# cmoy.net
KiCad netlist of a schematic drawn in EAGLE
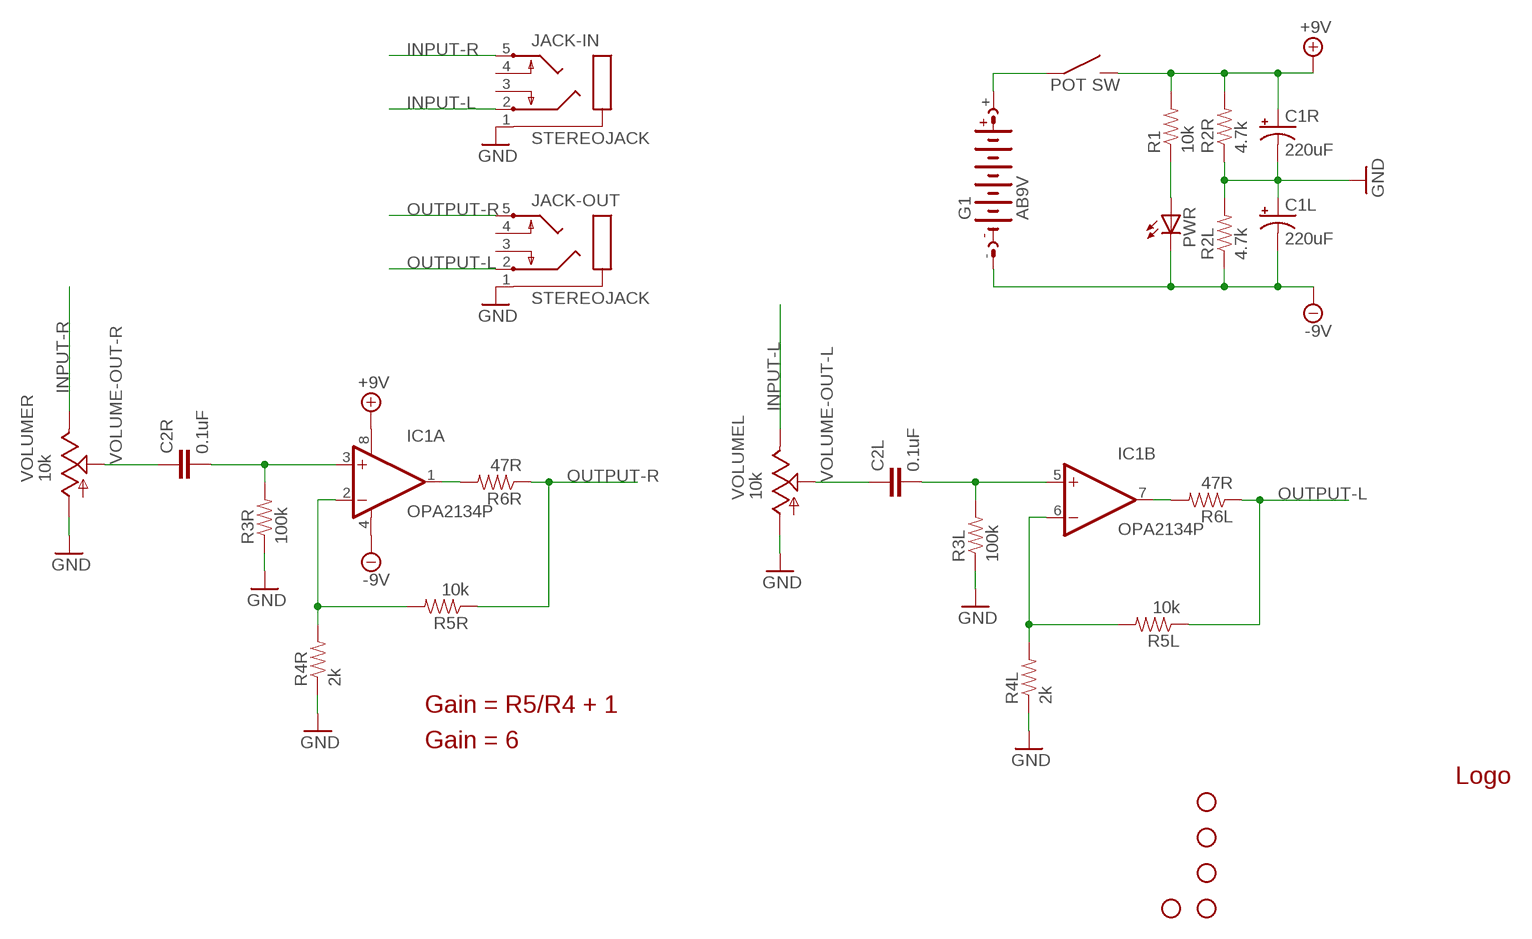
[diagram p0: schematic, sheet 1]

(export (version "E")
  (design (tool "Eeschema 10.0.6"))
  (components
    (comp (ref "C1L")
      (value "220uF")
      (footprint "eagle-import:CPOL-RADIAL-6.3MM")
      (libsource (lib "eagle-import") (part "CAP_POL-RADIAL-6.3MM"))
    )
    (comp (ref "C1R")
      (value "220uF")
      (footprint "eagle-import:CPOL-RADIAL-6.3MM")
      (libsource (lib "eagle-import") (part "CAP_POL-RADIAL-6.3MM"))
    )
    (comp (ref "C2L")
      (value "0.1uF")
      (footprint "eagle-import:CAP-PTH-VIMA-MKS2C031001A00KSSD")
      (libsource (lib "eagle-import") (part "CAP-VIMA-MKS2D031001"))
    )
    (comp (ref "C2R")
      (value "0.1uF")
      (footprint "eagle-import:CAP-PTH-VIMA-MKS2C031001A00KSSD")
      (libsource (lib "eagle-import") (part "CAP-VIMA-MKS2D031001"))
    )
    (comp (ref "G1")
      (value "AB9V")
      (footprint "eagle-import:AB9V")
      (libsource (lib "eagle-import") (part "AB9V"))
    )
    (comp (ref "IC1")
      (value "OPA2134P")
      (footprint "eagle-import:DIL-8")
      (libsource (lib "eagle-import") (part "OPA2134P"))
    )
    (comp (ref "JACK-IN")
      (value "STEREOJACK")
      (footprint "eagle-import:STX3100")
      (libsource (lib "eagle-import") (part "STEREOJACK"))
    )
    (comp (ref "JACK-OUT")
      (value "STEREOJACK")
      (footprint "eagle-import:STX3100")
      (libsource (lib "eagle-import") (part "STEREOJACK"))
    )
    (comp (ref "JP1")
      (value "STAND-OFF")
      (footprint "eagle-import:STAND-OFF")
      (libsource (lib "eagle-import") (part "STAND-OFF"))
    )
    (comp (ref "JP2")
      (value "STAND-OFF")
      (footprint "eagle-import:STAND-OFF")
      (libsource (lib "eagle-import") (part "STAND-OFF"))
    )
    (comp (ref "JP3")
      (value "STAND-OFF")
      (footprint "eagle-import:STAND-OFF")
      (libsource (lib "eagle-import") (part "STAND-OFF"))
    )
    (comp (ref "JP4")
      (value "STAND-OFF")
      (footprint "eagle-import:STAND-OFF")
      (libsource (lib "eagle-import") (part "STAND-OFF"))
    )
    (comp (ref "JP5")
      (value "STAND-OFF")
      (footprint "eagle-import:STAND-OFF")
      (libsource (lib "eagle-import") (part "STAND-OFF"))
    )
    (comp (ref "PWR")
      (value "LED-3MM-MINUS")
      (footprint "eagle-import:LED3MM-MINUS")
      (libsource (lib "eagle-import") (part "LED-3MM-MINUS"))
    )
    (comp (ref "R1")
      (value "10k")
      (footprint "eagle-import:1_6W-RES-OUTLINE")
      (libsource (lib "eagle-import") (part "RESISTOR-PTH-1/6W-OUTLINE"))
    )
    (comp (ref "R2L")
      (value "4.7k")
      (footprint "eagle-import:1_6W-RES-OUTLINE")
      (libsource (lib "eagle-import") (part "RESISTOR-PTH-1/6W-OUTLINE"))
    )
    (comp (ref "R2R")
      (value "4.7k")
      (footprint "eagle-import:1_6W-RES-OUTLINE")
      (libsource (lib "eagle-import") (part "RESISTOR-PTH-1/6W-OUTLINE"))
    )
    (comp (ref "R3L")
      (value "100k")
      (footprint "eagle-import:1_4W-RES-OUTLINE")
      (libsource (lib "eagle-import") (part "RESISTOR-PTH-1/4W-OUTLINE"))
    )
    (comp (ref "R3R")
      (value "100k")
      (footprint "eagle-import:1_4W-RES-OUTLINE")
      (libsource (lib "eagle-import") (part "RESISTOR-PTH-1/4W-OUTLINE"))
    )
    (comp (ref "R4L")
      (value "2k")
      (footprint "eagle-import:1_4W-RES-OUTLINE")
      (libsource (lib "eagle-import") (part "RESISTOR-PTH-1/4W-OUTLINE"))
    )
    (comp (ref "R4R")
      (value "2k")
      (footprint "eagle-import:1_4W-RES-OUTLINE")
      (libsource (lib "eagle-import") (part "RESISTOR-PTH-1/4W-OUTLINE"))
    )
    (comp (ref "R5L")
      (value "10k")
      (footprint "eagle-import:1_4W-RES-OUTLINE")
      (libsource (lib "eagle-import") (part "RESISTOR-PTH-1/4W-OUTLINE"))
    )
    (comp (ref "R5R")
      (value "10k")
      (footprint "eagle-import:1_4W-RES-OUTLINE")
      (libsource (lib "eagle-import") (part "RESISTOR-PTH-1/4W-OUTLINE"))
    )
    (comp (ref "R6L")
      (value "47R")
      (footprint "eagle-import:1_4W-RES-OUTLINE")
      (libsource (lib "eagle-import") (part "RESISTOR-PTH-1/4W-OUTLINE"))
    )
    (comp (ref "R6R")
      (value "47R")
      (footprint "eagle-import:1_4W-RES-OUTLINE")
      (libsource (lib "eagle-import") (part "RESISTOR-PTH-1/4W-OUTLINE"))
    )
    (comp (ref "U$1")
      (value "OSHW-LOGO-OUTLINE")
      (footprint "eagle-import:OSHW-LOGO-OUTLINE")
      (libsource (lib "eagle-import") (part "OSHW-LOGO-OUTLINE"))
    )
    (comp (ref "VOLUME")
      (value "10k")
      (footprint "eagle-import:ALPS_RK0971221Z0X")
      (libsource (lib "eagle-import") (part "ALPS_RK0971221Z0N"))
    )
  )
  (nets
    (net (code "1") (name "+9V") (class "Default")
      (node (ref "C1R") (pin "1") (pinfunction "+_1") (pintype "passive"))
      (node (ref "IC1") (pin "8") (pinfunction "V+_8") (pintype "power_in"))
      (node (ref "R1") (pin "2") (pinfunction "2_2") (pintype "passive"))
      (node (ref "R2R") (pin "2") (pinfunction "2_2") (pintype "passive"))
      (node (ref "VOLUME") (pin "S2") (pinfunction "S2_S2") (pintype "power_in"))
    )
    (net (code "2") (name "-9V") (class "Default")
      (node (ref "C1L") (pin "2") (pinfunction "-_2") (pintype "passive"))
      (node (ref "G1") (pin "-") (pinfunction "-_-") (pintype "passive"))
      (node (ref "IC1") (pin "4") (pinfunction "V-_4") (pintype "power_in"))
      (node (ref "PWR") (pin "K") (pinfunction "C_K") (pintype "passive"))
      (node (ref "R2L") (pin "1") (pinfunction "1_1") (pintype "passive"))
    )
    (net (code "3") (name "/INPUT-L") (class "Default")
      (node (ref "JACK-IN") (pin "2") (pinfunction "2_2") (pintype "passive"))
      (node (ref "VOLUME") (pin "I1") (pinfunction "3_I1") (pintype "passive"))
    )
    (net (code "4") (name "/INPUT-R") (class "Default")
      (node (ref "JACK-IN") (pin "5") (pinfunction "5_5") (pintype "passive"))
      (node (ref "VOLUME") (pin "I2") (pinfunction "3_I2") (pintype "passive"))
    )
    (net (code "5") (name "/OUTPUT-L") (class "Default")
      (node (ref "JACK-OUT") (pin "2") (pinfunction "2_2") (pintype "passive"))
      (node (ref "R5L") (pin "P$1") (pinfunction "1_P$1") (pintype "passive"))
      (node (ref "R6L") (pin "P$1") (pinfunction "1_P$1") (pintype "passive"))
    )
    (net (code "6") (name "/OUTPUT-R") (class "Default")
      (node (ref "JACK-OUT") (pin "5") (pinfunction "5_5") (pintype "passive"))
      (node (ref "R5R") (pin "P$1") (pinfunction "1_P$1") (pintype "passive"))
      (node (ref "R6R") (pin "P$1") (pinfunction "1_P$1") (pintype "passive"))
    )
    (net (code "7") (name "/VOLUME-OUT-L") (class "Default")
      (node (ref "C2L") (pin "1") (pinfunction "1_1") (pintype "passive"))
      (node (ref "VOLUME") (pin "O1") (pinfunction "2_O1") (pintype "passive"))
    )
    (net (code "8") (name "/VOLUME-OUT-R") (class "Default")
      (node (ref "C2R") (pin "1") (pinfunction "1_1") (pintype "passive"))
      (node (ref "VOLUME") (pin "O2") (pinfunction "2_O2") (pintype "passive"))
    )
    (net (code "9") (name "GND") (class "Default")
      (node (ref "C1L") (pin "1") (pinfunction "+_1") (pintype "passive"))
      (node (ref "C1R") (pin "2") (pinfunction "-_2") (pintype "passive"))
      (node (ref "JACK-IN") (pin "1") (pinfunction "1_1") (pintype "passive"))
      (node (ref "JACK-OUT") (pin "1") (pinfunction "1_1") (pintype "passive"))
      (node (ref "R2L") (pin "2") (pinfunction "2_2") (pintype "passive"))
      (node (ref "R2R") (pin "1") (pinfunction "1_1") (pintype "passive"))
      (node (ref "R3L") (pin "P$1") (pinfunction "1_P$1") (pintype "passive"))
      (node (ref "R3R") (pin "P$1") (pinfunction "1_P$1") (pintype "passive"))
      (node (ref "R4L") (pin "P$1") (pinfunction "1_P$1") (pintype "passive"))
      (node (ref "R4R") (pin "P$1") (pinfunction "1_P$1") (pintype "passive"))
      (node (ref "VOLUME") (pin "G1") (pinfunction "1_G1") (pintype "passive"))
      (node (ref "VOLUME") (pin "G2") (pinfunction "1_G2") (pintype "passive"))
    )
    (net (code "10") (name "Net-(G1-Pad+)") (class "Default")
      (node (ref "G1") (pin "+") (pinfunction "+_+") (pintype "passive"))
      (node (ref "VOLUME") (pin "S1") (pinfunction "S1_S1") (pintype "power_in"))
    )
    (net (code "11") (name "Net-(IC1A-+IN)") (class "Default")
      (node (ref "C2R") (pin "2") (pinfunction "2_2") (pintype "passive"))
      (node (ref "IC1") (pin "3") (pinfunction "+IN_3") (pintype "input"))
      (node (ref "R3R") (pin "P$2") (pinfunction "2_P$2") (pintype "passive"))
    )
    (net (code "12") (name "Net-(IC1A--IN)") (class "Default")
      (node (ref "IC1") (pin "2") (pinfunction "-IN_2") (pintype "input"))
      (node (ref "R4R") (pin "P$2") (pinfunction "2_P$2") (pintype "passive"))
      (node (ref "R5R") (pin "P$2") (pinfunction "2_P$2") (pintype "passive"))
    )
    (net (code "13") (name "Net-(IC1A-OUT)") (class "Default")
      (node (ref "IC1") (pin "1") (pinfunction "OUT_1") (pintype "output"))
      (node (ref "R6R") (pin "P$2") (pinfunction "2_P$2") (pintype "passive"))
    )
    (net (code "14") (name "Net-(IC1B-+IN)") (class "Default")
      (node (ref "C2L") (pin "2") (pinfunction "2_2") (pintype "passive"))
      (node (ref "IC1") (pin "5") (pinfunction "+IN_5") (pintype "input"))
      (node (ref "R3L") (pin "P$2") (pinfunction "2_P$2") (pintype "passive"))
    )
    (net (code "15") (name "Net-(IC1B--IN)") (class "Default")
      (node (ref "IC1") (pin "6") (pinfunction "-IN_6") (pintype "input"))
      (node (ref "R4L") (pin "P$2") (pinfunction "2_P$2") (pintype "passive"))
      (node (ref "R5L") (pin "P$2") (pinfunction "2_P$2") (pintype "passive"))
    )
    (net (code "16") (name "Net-(IC1B-OUT)") (class "Default")
      (node (ref "IC1") (pin "7") (pinfunction "OUT_7") (pintype "output"))
      (node (ref "R6L") (pin "P$2") (pinfunction "2_P$2") (pintype "passive"))
    )
    (net (code "17") (name "Net-(PWR-PadA)") (class "Default")
      (node (ref "PWR") (pin "A") (pinfunction "A_A") (pintype "passive"))
      (node (ref "R1") (pin "1") (pinfunction "1_1") (pintype "passive"))
    )
    (net (code "18") (name "unconnected-(JACK-IN-Pad3)") (class "Default")
      (node (ref "JACK-IN") (pin "3") (pinfunction "3_3") (pintype "passive"))
    )
    (net (code "19") (name "unconnected-(JACK-IN-Pad4)") (class "Default")
      (node (ref "JACK-IN") (pin "4") (pinfunction "4_4") (pintype "passive"))
    )
    (net (code "20") (name "unconnected-(JACK-OUT-Pad3)") (class "Default")
      (node (ref "JACK-OUT") (pin "3") (pinfunction "3_3") (pintype "passive"))
    )
    (net (code "21") (name "unconnected-(JACK-OUT-Pad4)") (class "Default")
      (node (ref "JACK-OUT") (pin "4") (pinfunction "4_4") (pintype "passive"))
    )
  )
)
